# strip.net
KiCad netlist of a schematic drawn in EAGLE
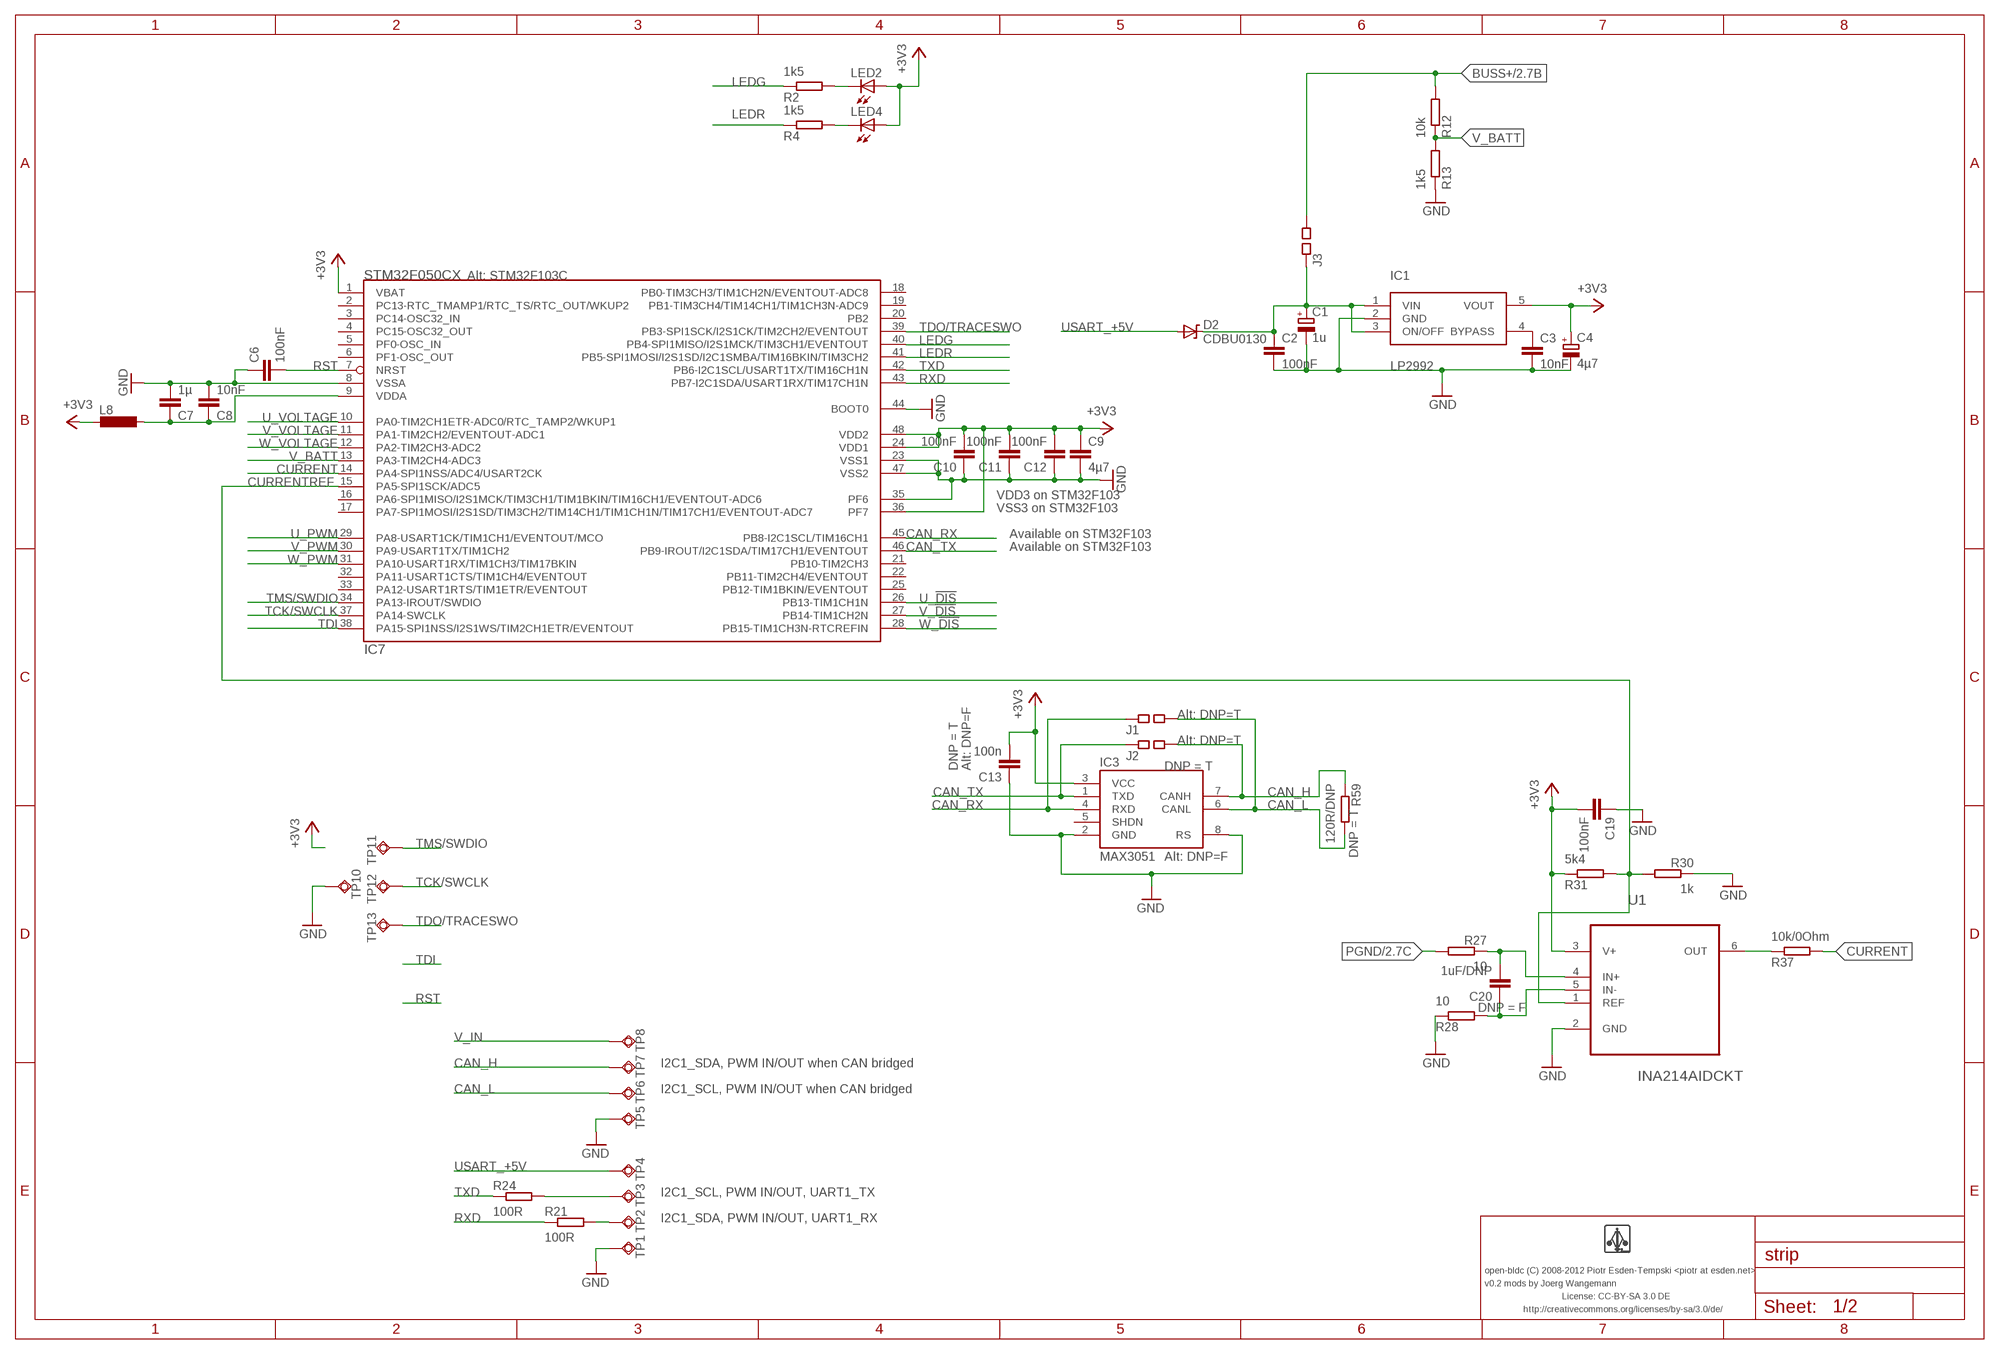
[diagram p0: schematic, sheet 1]
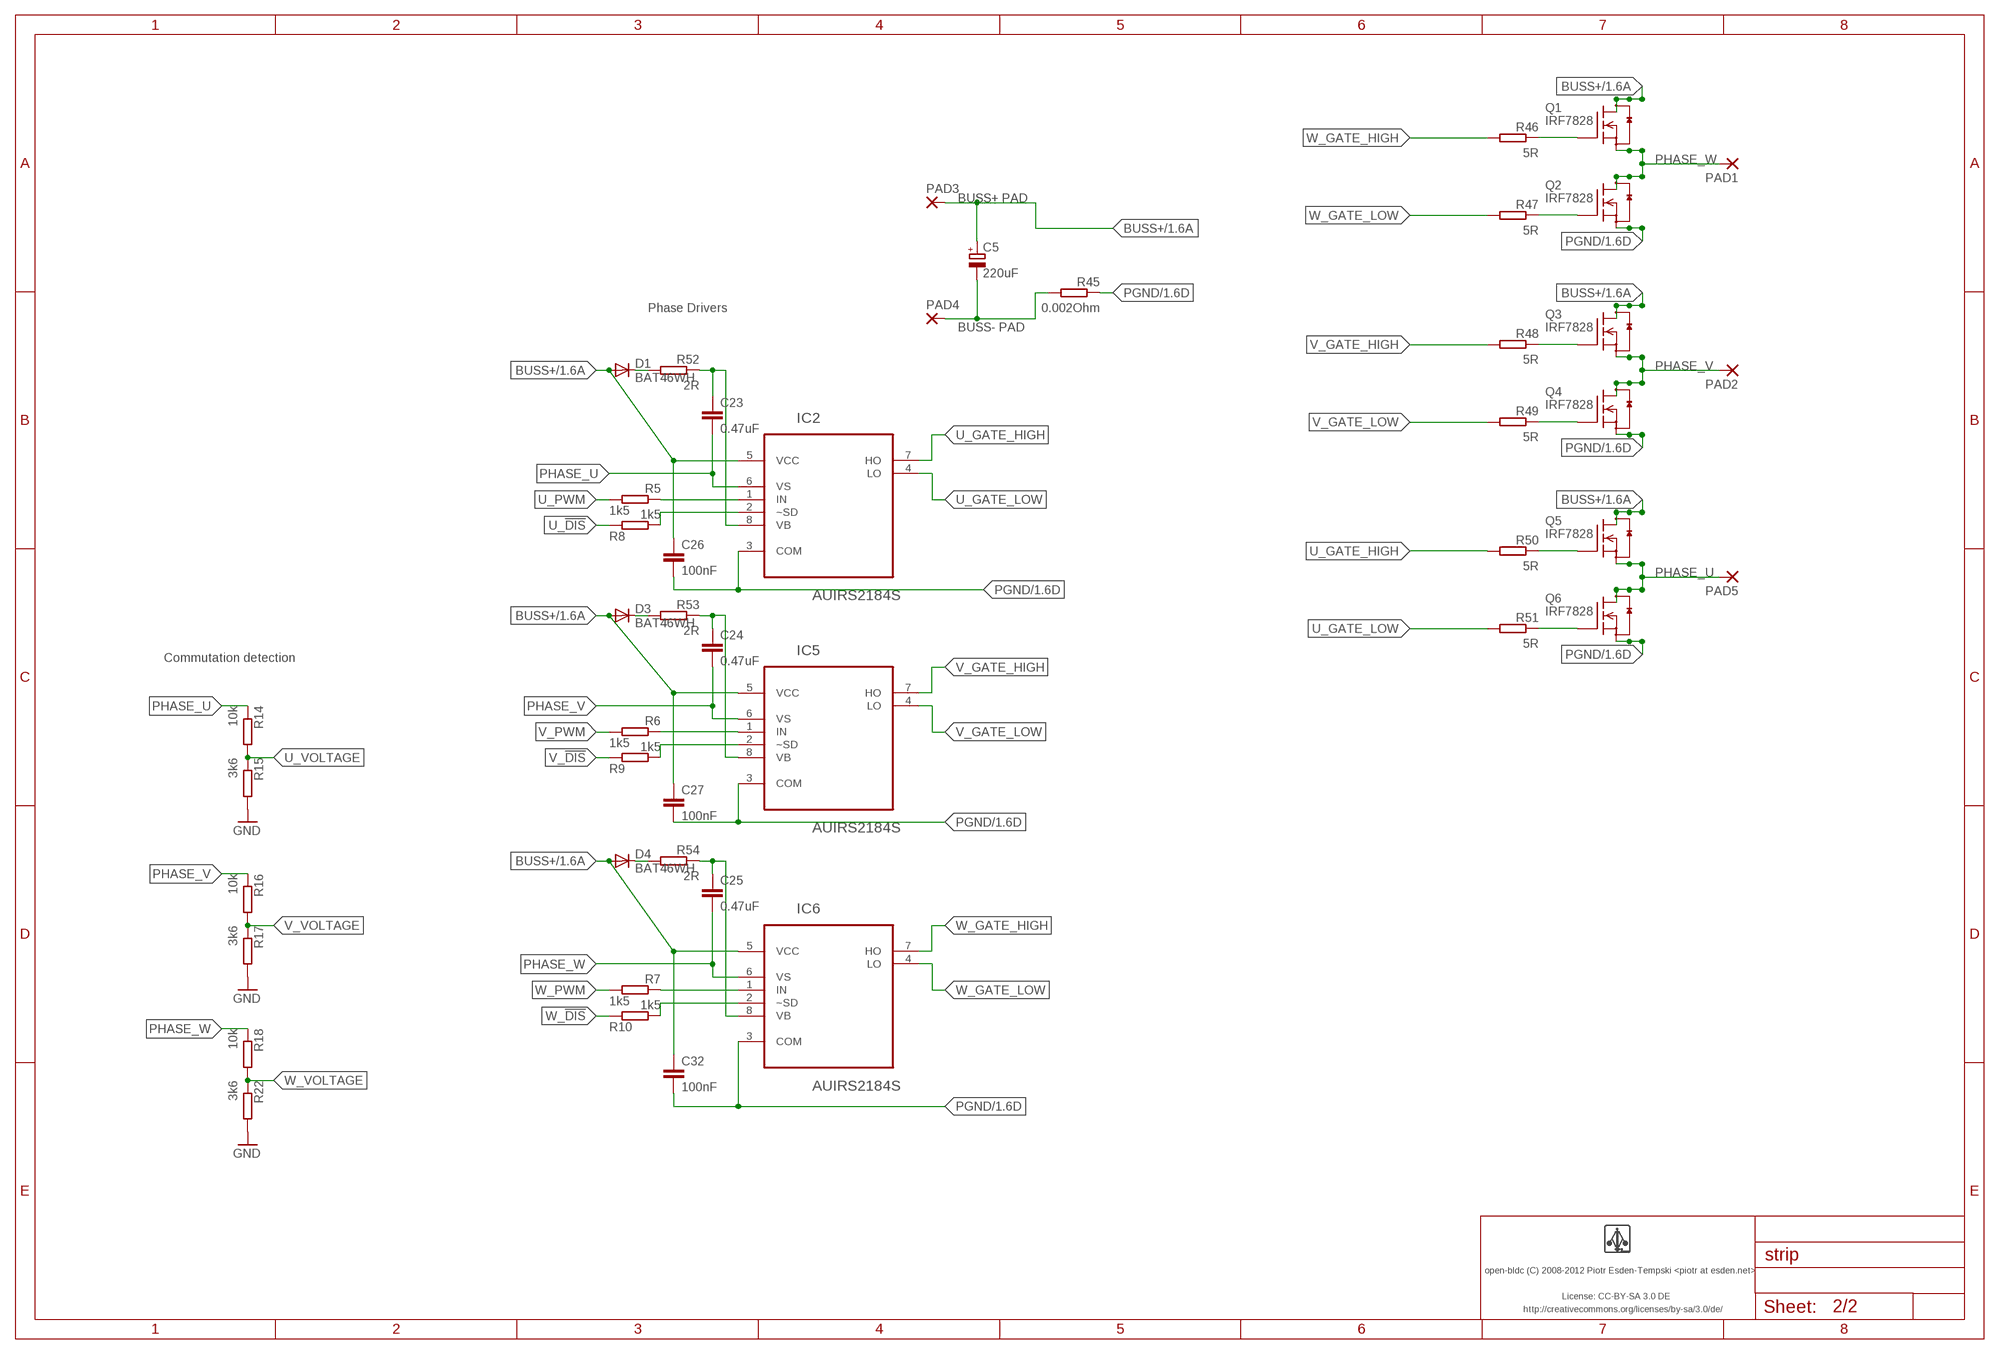
[diagram p1: schematic, sheet 2]

(export (version "E")
  (design (tool "Eeschema 10.0.6"))
  (components
    (comp (ref "C5")
      (value "220uF")
      (footprint "eagle-import:7343_D")
      (fields (field (name "PARTNO") "cap-tan-D-220u-16v"))
      (libsource (lib "eagle-import") (part "CAPACITOR-POLD"))
    )
    (comp (ref "C23")
      (value "0.47uF")
      (footprint "eagle-import:0603-CAP")
      (fields (field (name "PARTNO") "cap-tan-0603-1u"))
      (libsource (lib "eagle-import") (part "CAPACITOR-0603"))
    )
    (comp (ref "C24")
      (value "0.47uF")
      (footprint "eagle-import:0603-CAP")
      (fields (field (name "PARTNO") "cap-tan-0603-1u"))
      (libsource (lib "eagle-import") (part "CAPACITOR-0603"))
    )
    (comp (ref "C25")
      (value "0.47uF")
      (footprint "eagle-import:0603-CAP")
      (fields (field (name "PARTNO") "cap-tan-0603-1u"))
      (libsource (lib "eagle-import") (part "CAPACITOR-0603"))
    )
    (comp (ref "C26")
      (value "100nF")
      (footprint "eagle-import:0603-CAP")
      (fields (field (name "PARTNO") "cap-cer-0402-100n"))
      (libsource (lib "eagle-import") (part "CAPACITOR-0603"))
    )
    (comp (ref "C27")
      (value "100nF")
      (footprint "eagle-import:0603-CAP")
      (fields (field (name "PARTNO") "cap-cer-0402-100n"))
      (libsource (lib "eagle-import") (part "CAPACITOR-0603"))
    )
    (comp (ref "C32")
      (value "100nF")
      (footprint "eagle-import:0603-CAP")
      (fields (field (name "PARTNO") "cap-cer-0402-100n"))
      (libsource (lib "eagle-import") (part "CAPACITOR-0603"))
    )
    (comp (ref "D1")
      (value "BAT46WH")
      (footprint "eagle-import:SOD-123-DIO")
      (libsource (lib "eagle-import") (part "DIODE-SOD-123"))
    )
    (comp (ref "D3")
      (value "BAT46WH")
      (footprint "eagle-import:SOD-123-DIO")
      (libsource (lib "eagle-import") (part "DIODE-SOD-123"))
    )
    (comp (ref "D4")
      (value "BAT46WH")
      (footprint "eagle-import:SOD-123-DIO")
      (libsource (lib "eagle-import") (part "DIODE-SOD-123"))
    )
    (comp (ref "IC2")
      (value "AUIRS2184S")
      (footprint "eagle-import:SOIC127P600X175-8N")
      (fields (field (name "PARTNO") "ic-so8-mosfet-driver-buck"))
      (libsource (lib "eagle-import") (part "AUIRS2184S"))
    )
    (comp (ref "IC5")
      (value "AUIRS2184S")
      (footprint "eagle-import:SOIC127P600X175-8N")
      (fields (field (name "PARTNO") "ic-so8-mosfet-driver-buck"))
      (libsource (lib "eagle-import") (part "AUIRS2184S"))
    )
    (comp (ref "IC6")
      (value "AUIRS2184S")
      (footprint "eagle-import:SOIC127P600X175-8N")
      (fields (field (name "PARTNO") "ic-so8-mosfet-driver-buck"))
      (libsource (lib "eagle-import") (part "AUIRS2184S"))
    )
    (comp (ref "PAD1")
      (value "SMD5")
      (footprint "eagle-import:SMD2,54-5,08")
      (libsource (lib "eagle-import") (part "SMD5"))
    )
    (comp (ref "PAD2")
      (value "SMD5")
      (footprint "eagle-import:SMD2,54-5,08")
      (libsource (lib "eagle-import") (part "SMD5"))
    )
    (comp (ref "PAD3")
      (value "SMD5")
      (footprint "eagle-import:SMD2,54-5,08")
      (libsource (lib "eagle-import") (part "SMD5"))
    )
    (comp (ref "PAD4")
      (value "SMD5")
      (footprint "eagle-import:SMD2,54-5,08")
      (libsource (lib "eagle-import") (part "SMD5"))
    )
    (comp (ref "PAD5")
      (value "SMD5")
      (footprint "eagle-import:SMD2,54-5,08")
      (libsource (lib "eagle-import") (part "SMD5"))
    )
    (comp (ref "Q1")
      (value "IRF7828")
      (footprint "eagle-import:SO8")
      (fields (field (name "PARTNO") "ic-so8-mosfet-n-ch-30v-15a"))
      (libsource (lib "eagle-import") (part "IRF7828"))
    )
    (comp (ref "Q2")
      (value "IRF7828")
      (footprint "eagle-import:SO8")
      (fields (field (name "PARTNO") "ic-so8-mosfet-n-ch-30v-15a"))
      (libsource (lib "eagle-import") (part "IRF7828"))
    )
    (comp (ref "Q3")
      (value "IRF7828")
      (footprint "eagle-import:SO8")
      (fields (field (name "PARTNO") "ic-so8-mosfet-n-ch-30v-15a"))
      (libsource (lib "eagle-import") (part "IRF7828"))
    )
    (comp (ref "Q4")
      (value "IRF7828")
      (footprint "eagle-import:SO8")
      (fields (field (name "PARTNO") "ic-so8-mosfet-n-ch-30v-15a"))
      (libsource (lib "eagle-import") (part "IRF7828"))
    )
    (comp (ref "Q5")
      (value "IRF7828")
      (footprint "eagle-import:SO8")
      (fields (field (name "PARTNO") "ic-so8-mosfet-n-ch-30v-15a"))
      (libsource (lib "eagle-import") (part "IRF7828"))
    )
    (comp (ref "Q6")
      (value "IRF7828")
      (footprint "eagle-import:SO8")
      (fields (field (name "PARTNO") "ic-so8-mosfet-n-ch-30v-15a"))
      (libsource (lib "eagle-import") (part "IRF7828"))
    )
    (comp (ref "R5")
      (value "1k5")
      (footprint "eagle-import:0402-RES")
      (fields (field (name "PARTNO") "res-0402-1k5"))
      (libsource (lib "eagle-import") (part "RESISTOR-0402"))
    )
    (comp (ref "R6")
      (value "1k5")
      (footprint "eagle-import:0402-RES")
      (fields (field (name "PARTNO") "res-0402-1k5"))
      (libsource (lib "eagle-import") (part "RESISTOR-0402"))
    )
    (comp (ref "R7")
      (value "1k5")
      (footprint "eagle-import:0402-RES")
      (fields (field (name "PARTNO") "res-0402-1k5"))
      (libsource (lib "eagle-import") (part "RESISTOR-0402"))
    )
    (comp (ref "R8")
      (value "1k5")
      (footprint "eagle-import:0402-RES")
      (fields (field (name "PARTNO") "res-0402-1k5"))
      (libsource (lib "eagle-import") (part "RESISTOR-0402"))
    )
    (comp (ref "R9")
      (value "1k5")
      (footprint "eagle-import:0402-RES")
      (fields (field (name "PARTNO") "res-0402-1k5"))
      (libsource (lib "eagle-import") (part "RESISTOR-0402"))
    )
    (comp (ref "R10")
      (value "1k5")
      (footprint "eagle-import:0402-RES")
      (fields (field (name "PARTNO") "res-0402-1k5"))
      (libsource (lib "eagle-import") (part "RESISTOR-0402"))
    )
    (comp (ref "R14")
      (value "10k")
      (footprint "eagle-import:0402-RES")
      (fields (field (name "PARTNO") "res-0402-10k"))
      (libsource (lib "eagle-import") (part "RESISTOR-0402"))
    )
    (comp (ref "R15")
      (value "3k6")
      (footprint "eagle-import:0402-RES")
      (libsource (lib "eagle-import") (part "RESISTOR-0402"))
    )
    (comp (ref "R16")
      (value "10k")
      (footprint "eagle-import:0402-RES")
      (fields (field (name "PARTNO") "res-0402-10k"))
      (libsource (lib "eagle-import") (part "RESISTOR-0402"))
    )
    (comp (ref "R17")
      (value "3k6")
      (footprint "eagle-import:0402-RES")
      (libsource (lib "eagle-import") (part "RESISTOR-0402"))
    )
    (comp (ref "R18")
      (value "10k")
      (footprint "eagle-import:0402-RES")
      (fields (field (name "PARTNO") "res-0402-10k"))
      (libsource (lib "eagle-import") (part "RESISTOR-0402"))
    )
    (comp (ref "R22")
      (value "3k6")
      (footprint "eagle-import:0402-RES")
      (libsource (lib "eagle-import") (part "RESISTOR-0402"))
    )
    (comp (ref "R45")
      (value "0.002Ohm")
      (footprint "eagle-import:1206-RES")
      (fields (field (name "PARTNO") "res-1206-0005"))
      (libsource (lib "eagle-import") (part "RESISTOR-1206"))
    )
    (comp (ref "R46")
      (value "5R")
      (footprint "eagle-import:0603-RES")
      (fields (field (name "PARTNO") "res-0402-10"))
      (libsource (lib "eagle-import") (part "RESISTOR-0603"))
    )
    (comp (ref "R47")
      (value "5R")
      (footprint "eagle-import:0603-RES")
      (fields (field (name "PARTNO") "res-0402-10"))
      (libsource (lib "eagle-import") (part "RESISTOR-0603"))
    )
    (comp (ref "R48")
      (value "5R")
      (footprint "eagle-import:0603-RES")
      (fields (field (name "PARTNO") "res-0402-10"))
      (libsource (lib "eagle-import") (part "RESISTOR-0603"))
    )
    (comp (ref "R49")
      (value "5R")
      (footprint "eagle-import:0603-RES")
      (fields (field (name "PARTNO") "res-0402-10"))
      (libsource (lib "eagle-import") (part "RESISTOR-0603"))
    )
    (comp (ref "R50")
      (value "5R")
      (footprint "eagle-import:0603-RES")
      (fields (field (name "PARTNO") "res-0402-10"))
      (libsource (lib "eagle-import") (part "RESISTOR-0603"))
    )
    (comp (ref "R51")
      (value "5R")
      (footprint "eagle-import:0603-RES")
      (fields (field (name "PARTNO") "res-0402-10"))
      (libsource (lib "eagle-import") (part "RESISTOR-0603"))
    )
    (comp (ref "R52")
      (value "2R")
      (footprint "eagle-import:0402-RES")
      (fields (field (name "PARTNO") "res-0402-10"))
      (libsource (lib "eagle-import") (part "RESISTOR-0402"))
    )
    (comp (ref "R53")
      (value "2R")
      (footprint "eagle-import:0402-RES")
      (fields (field (name "PARTNO") "res-0402-10"))
      (libsource (lib "eagle-import") (part "RESISTOR-0402"))
    )
    (comp (ref "R54")
      (value "2R")
      (footprint "eagle-import:0402-RES")
      (fields (field (name "PARTNO") "res-0402-10"))
      (libsource (lib "eagle-import") (part "RESISTOR-0402"))
    )
    (comp (ref "U$2")
      (value "LOGO")
      (footprint "eagle-import:LOGO_SILK_SMALL")
      (libsource (lib "eagle-import") (part "LOGO-SILK-SMALL"))
    )
    (comp (ref "C1")
      (value "1u")
      (footprint "eagle-import:0805-POL-CAP")
      (fields (field (name "PARTNO") "cap-cer-0805-1u-35v"))
      (libsource (lib "eagle-import") (part "CAPACITOR-POL-0805"))
    )
    (comp (ref "C2")
      (value "100nF")
      (footprint "eagle-import:0402-CAP")
      (fields (field (name "PARTNO") "cap-cer-0402-100n"))
      (libsource (lib "eagle-import") (part "CAPACITOR-0402"))
    )
    (comp (ref "C3")
      (value "10nF")
      (footprint "eagle-import:0402-CAP")
      (fields (field (name "PARTNO") "cap-cer-0402-10n"))
      (libsource (lib "eagle-import") (part "CAPACITOR-0402"))
    )
    (comp (ref "C4")
      (value "4µ7")
      (footprint "eagle-import:0805-POL-CAP")
      (fields (field (name "PARTNO") "cap-cer-0805-4u7-16v"))
      (libsource (lib "eagle-import") (part "CAPACITOR-POL-0805"))
    )
    (comp (ref "C6")
      (value "100nF")
      (footprint "eagle-import:0402-CAP")
      (fields (field (name "PARTNO") "cap-cer-0402-100n"))
      (libsource (lib "eagle-import") (part "CAPACITOR-0402"))
    )
    (comp (ref "C7")
      (value "1µ")
      (footprint "eagle-import:0402-CAP")
      (fields (field (name "PARTNO") "cap-cer-0402-1u"))
      (libsource (lib "eagle-import") (part "CAPACITOR-0402"))
    )
    (comp (ref "C8")
      (value "10nF")
      (footprint "eagle-import:0402-CAP")
      (fields (field (name "PARTNO") "cap-cer-0402-10n"))
      (libsource (lib "eagle-import") (part "CAPACITOR-0402"))
    )
    (comp (ref "C9")
      (value "4µ7")
      (footprint "eagle-import:0805-CAP")
      (fields (field (name "PARTNO") "cap-cer-0805-4u7"))
      (libsource (lib "eagle-import") (part "CAPACITOR-0805"))
    )
    (comp (ref "C10")
      (value "100nF")
      (footprint "eagle-import:0402-CAP")
      (fields (field (name "PARTNO") "cap-cer-0402-100n"))
      (libsource (lib "eagle-import") (part "CAPACITOR-0402"))
    )
    (comp (ref "C11")
      (value "100nF")
      (footprint "eagle-import:0402-CAP")
      (fields (field (name "PARTNO") "cap-cer-0402-100n"))
      (libsource (lib "eagle-import") (part "CAPACITOR-0402"))
    )
    (comp (ref "C12")
      (value "100nF")
      (footprint "eagle-import:0402-CAP")
      (fields (field (name "PARTNO") "cap-cer-0402-100n"))
      (libsource (lib "eagle-import") (part "CAPACITOR-0402"))
    )
    (comp (ref "C13")
      (value "100n")
      (footprint "eagle-import:0402-CAP")
      (fields (field (name "DNP") "T") (field (name "PARTNO") "cap-cer-0402-100n"))
      (libsource (lib "eagle-import") (part "CAPACITOR-0402"))
    )
    (comp (ref "C19")
      (value "100nF")
      (footprint "eagle-import:0402-CAP")
      (fields (field (name "PARTNO") "cap-cer-0402-100n"))
      (libsource (lib "eagle-import") (part "CAPACITOR-0402"))
    )
    (comp (ref "C20")
      (value "1uF/DNP")
      (footprint "eagle-import:0603-CAP")
      (fields (field (name "DNP") "F") (field (name "PARTNO") "cap-cer-0402-100n"))
      (libsource (lib "eagle-import") (part "CAPACITOR-0603"))
    )
    (comp (ref "D2")
      (value "CDBU0130")
      (footprint "eagle-import:0603-DIO")
      (fields (field (name "PARTNO") "diode-0603"))
      (libsource (lib "eagle-import") (part "DIODE-ZENER-0603"))
    )
    (comp (ref "IC1")
      (value "LP2992")
      (footprint "eagle-import:SOT23-5")
      (fields (field (name "PARTNO") "vreg-sot-23-5-3v3"))
      (libsource (lib "eagle-import") (part "LP2992"))
    )
    (comp (ref "IC3")
      (value "MAX3051")
      (footprint "eagle-import:SO8")
      (fields (field (name "DNP") "T"))
      (libsource (lib "eagle-import") (part "MAX3051"))
    )
    (comp (ref "IC7")
      (value "STM32F050CX")
      (footprint "eagle-import:LQFP48")
      (fields (field (name "PARTNO") "mcu-tqfp-32-stm32f05"))
      (libsource (lib "eagle-import") (part "STM32F050CX"))
    )
    (comp (ref "J1")
      (value "SQ_JMP-0402")
      (footprint "eagle-import:0402-SQJMP")
      (fields (field (name "PARTNO") "res-0402-0"))
      (libsource (lib "eagle-import") (part "SQ_JMP-0402"))
    )
    (comp (ref "J2")
      (value "SQ_JMP-0402")
      (footprint "eagle-import:0402-SQJMP")
      (fields (field (name "PARTNO") "res-0402-0"))
      (libsource (lib "eagle-import") (part "SQ_JMP-0402"))
    )
    (comp (ref "J3")
      (value "SQ_JMP-0402")
      (footprint "eagle-import:0402-SQJMP")
      (fields (field (name "PARTNO") "res-0402-0"))
      (libsource (lib "eagle-import") (part "SQ_JMP-0402"))
    )
    (comp (ref "L8")
      (value "INDUCTOR-0603")
      (footprint "eagle-import:0603-IND")
      (fields (field (name "PARTNO") "ferrite-0603-600ohm"))
      (libsource (lib "eagle-import") (part "INDUCTOR-0603"))
    )
    (comp (ref "LED2")
      (value "GREEN")
      (footprint "eagle-import:0402-LED")
      (fields (field (name "PARTNO") "led-0402-green"))
      (libsource (lib "eagle-import") (part "LED-0402"))
    )
    (comp (ref "LED4")
      (value "RED")
      (footprint "eagle-import:0402-LED")
      (fields (field (name "PARTNO") "led-0402-green"))
      (libsource (lib "eagle-import") (part "LED-0402"))
    )
    (comp (ref "R2")
      (value "1k5")
      (footprint "eagle-import:0402-RES")
      (fields (field (name "PARTNO") "res-0402-1k5"))
      (libsource (lib "eagle-import") (part "RESISTOR-0402"))
    )
    (comp (ref "R4")
      (value "1k5")
      (footprint "eagle-import:0402-RES")
      (fields (field (name "PARTNO") "res-0402-1k5"))
      (libsource (lib "eagle-import") (part "RESISTOR-0402"))
    )
    (comp (ref "R12")
      (value "10k")
      (footprint "eagle-import:0402-RES")
      (fields (field (name "PARTNO") "res-0402-10k"))
      (libsource (lib "eagle-import") (part "RESISTOR-0402"))
    )
    (comp (ref "R13")
      (value "1k5")
      (footprint "eagle-import:0402-RES")
      (fields (field (name "PARTNO") "res-0402-1k5"))
      (libsource (lib "eagle-import") (part "RESISTOR-0402"))
    )
    (comp (ref "R21")
      (value "100R")
      (footprint "eagle-import:0402-RES")
      (fields (field (name "PARTNO") "res-0402-100"))
      (libsource (lib "eagle-import") (part "RESISTOR-0402"))
    )
    (comp (ref "R24")
      (value "100R")
      (footprint "eagle-import:0402-RES")
      (fields (field (name "PARTNO") "res-0402-100"))
      (libsource (lib "eagle-import") (part "RESISTOR-0402"))
    )
    (comp (ref "R27")
      (value "10")
      (footprint "eagle-import:0402-RES")
      (fields (field (name "PARTNO") "res-0402-665"))
      (libsource (lib "eagle-import") (part "RESISTOR-0402"))
    )
    (comp (ref "R28")
      (value "10")
      (footprint "eagle-import:0402-RES")
      (fields (field (name "PARTNO") "res-0402-560"))
      (libsource (lib "eagle-import") (part "RESISTOR-0402"))
    )
    (comp (ref "R30")
      (value "1k")
      (footprint "eagle-import:0402-RES")
      (fields (field (name "PARTNO") "res-0402-1k"))
      (libsource (lib "eagle-import") (part "RESISTOR-0402"))
    )
    (comp (ref "R31")
      (value "5k4")
      (footprint "eagle-import:0402-RES")
      (fields (field (name "PARTNO") "res-0402-5k36"))
      (libsource (lib "eagle-import") (part "RESISTOR-0402"))
    )
    (comp (ref "R37")
      (value "10k/0Ohm")
      (footprint "eagle-import:0402-RES")
      (fields (field (name "PARTNO") "res-0402-0"))
      (libsource (lib "eagle-import") (part "RESISTOR-0402"))
    )
    (comp (ref "R59")
      (value "120R/DNP")
      (footprint "eagle-import:0402-RES")
      (fields (field (name "DNP") "T") (field (name "PARTNO") "res-0402-60.4"))
      (libsource (lib "eagle-import") (part "RESISTOR-0402"))
    )
    (comp (ref "TP1")
      (value "TPSQTP20SQ")
      (footprint "eagle-import:TP20SQ")
      (libsource (lib "eagle-import") (part "TPSQTP20SQ"))
    )
    (comp (ref "TP2")
      (value "TPSQTP20SQ")
      (footprint "eagle-import:TP20SQ")
      (libsource (lib "eagle-import") (part "TPSQTP20SQ"))
    )
    (comp (ref "TP3")
      (value "TPSQTP20SQ")
      (footprint "eagle-import:TP20SQ")
      (libsource (lib "eagle-import") (part "TPSQTP20SQ"))
    )
    (comp (ref "TP4")
      (value "TPSQTP20SQ")
      (footprint "eagle-import:TP20SQ")
      (libsource (lib "eagle-import") (part "TPSQTP20SQ"))
    )
    (comp (ref "TP5")
      (value "TPSQTP20SQ")
      (footprint "eagle-import:TP20SQ")
      (libsource (lib "eagle-import") (part "TPSQTP20SQ"))
    )
    (comp (ref "TP6")
      (value "TPSQTP20SQ")
      (footprint "eagle-import:TP20SQ")
      (libsource (lib "eagle-import") (part "TPSQTP20SQ"))
    )
    (comp (ref "TP7")
      (value "TPSQTP20SQ")
      (footprint "eagle-import:TP20SQ")
      (libsource (lib "eagle-import") (part "TPSQTP20SQ"))
    )
    (comp (ref "TP8")
      (value "TPSQTP20SQ")
      (footprint "eagle-import:TP20SQ")
      (libsource (lib "eagle-import") (part "TPSQTP20SQ"))
    )
    (comp (ref "TP10")
      (value "TPSQTP11SQ")
      (footprint "eagle-import:TP11SQ")
      (libsource (lib "eagle-import") (part "TPSQTP11SQ"))
    )
    (comp (ref "TP11")
      (value "TPSQTP11SQ")
      (footprint "eagle-import:TP11SQ")
      (libsource (lib "eagle-import") (part "TPSQTP11SQ"))
    )
    (comp (ref "TP12")
      (value "TPSQTP11SQ")
      (footprint "eagle-import:TP11SQ")
      (libsource (lib "eagle-import") (part "TPSQTP11SQ"))
    )
    (comp (ref "TP13")
      (value "TPSQTP11SQ")
      (footprint "eagle-import:TP11SQ")
      (libsource (lib "eagle-import") (part "TPSQTP11SQ"))
    )
    (comp (ref "U$1")
      (value "LOGO")
      (footprint "eagle-import:LOGO_SILK_SMALL")
      (libsource (lib "eagle-import") (part "LOGO-SILK-SMALL"))
    )
    (comp (ref "U1")
      (value "INA214AIDCKT")
      (footprint "eagle-import:SOT65P210X110-6N")
      (libsource (lib "eagle-import") (part "INA214AIDCKT"))
    )
  )
  (nets
    (net (code "1") (name "+3V3") (class "Default")
      (node (ref "C10") (pin "P$2") (pinfunction "2_P$2") (pintype "passive"))
      (node (ref "C11") (pin "P$2") (pinfunction "2_P$2") (pintype "passive"))
      (node (ref "C12") (pin "P$2") (pinfunction "2_P$2") (pintype "passive"))
      (node (ref "C13") (pin "P$2") (pinfunction "2_P$2") (pintype "passive"))
      (node (ref "C19") (pin "P$2") (pinfunction "2_P$2") (pintype "passive"))
      (node (ref "C4") (pin "+") (pinfunction "+_+") (pintype "passive"))
      (node (ref "C9") (pin "P$1") (pinfunction "1_P$1") (pintype "passive"))
      (node (ref "IC1") (pin "5") (pinfunction "VOUT_5") (pintype "bidirectional"))
      (node (ref "IC3") (pin "3") (pinfunction "VCC_3") (pintype "bidirectional"))
      (node (ref "IC7") (pin "1") (pinfunction "VBAT_1") (pintype "power_in"))
      (node (ref "IC7") (pin "24") (pinfunction "VDD1_24") (pintype "power_in"))
      (node (ref "IC7") (pin "36") (pinfunction "PF7_36") (pintype "power_in"))
      (node (ref "IC7") (pin "48") (pinfunction "VDD2_48") (pintype "power_in"))
      (node (ref "L8") (pin "P$2") (pinfunction "2_P$2") (pintype "passive"))
      (node (ref "LED2") (pin "A") (pinfunction "A_A") (pintype "passive"))
      (node (ref "LED4") (pin "A") (pinfunction "A_A") (pintype "passive"))
      (node (ref "R31") (pin "P$1") (pinfunction "1_P$1") (pintype "passive"))
      (node (ref "U1") (pin "3") (pinfunction "V+_3") (pintype "power_in"))
    )
    (net (code "2") (name "BUSS+") (class "Default")
      (node (ref "C26") (pin "P$1") (pinfunction "1_P$1") (pintype "passive"))
      (node (ref "C27") (pin "P$1") (pinfunction "1_P$1") (pintype "passive"))
      (node (ref "C32") (pin "P$1") (pinfunction "1_P$1") (pintype "passive"))
      (node (ref "C5") (pin "+") (pinfunction "+_+") (pintype "passive"))
      (node (ref "D1") (pin "A") (pinfunction "A_A") (pintype "passive"))
      (node (ref "D3") (pin "A") (pinfunction "A_A") (pintype "passive"))
      (node (ref "D4") (pin "A") (pinfunction "A_A") (pintype "passive"))
      (node (ref "IC2") (pin "5") (pinfunction "VCC_5") (pintype "power_in"))
      (node (ref "IC5") (pin "5") (pinfunction "VCC_5") (pintype "power_in"))
      (node (ref "IC6") (pin "5") (pinfunction "VCC_5") (pintype "power_in"))
      (node (ref "J3") (pin "P$2") (pinfunction "2_P$2") (pintype "passive"))
      (node (ref "PAD3") (pin "1") (pinfunction "P_1") (pintype "passive"))
      (node (ref "Q1") (pin "5") (pinfunction "D1_5") (pintype "passive"))
      (node (ref "Q1") (pin "6") (pinfunction "D2_6") (pintype "passive"))
      (node (ref "Q1") (pin "7") (pinfunction "D3_7") (pintype "passive"))
      (node (ref "Q1") (pin "8") (pinfunction "D4_8") (pintype "passive"))
      (node (ref "Q3") (pin "5") (pinfunction "D1_5") (pintype "passive"))
      (node (ref "Q3") (pin "6") (pinfunction "D2_6") (pintype "passive"))
      (node (ref "Q3") (pin "7") (pinfunction "D3_7") (pintype "passive"))
      (node (ref "Q3") (pin "8") (pinfunction "D4_8") (pintype "passive"))
      (node (ref "Q5") (pin "5") (pinfunction "D1_5") (pintype "passive"))
      (node (ref "Q5") (pin "6") (pinfunction "D2_6") (pintype "passive"))
      (node (ref "Q5") (pin "7") (pinfunction "D3_7") (pintype "passive"))
      (node (ref "Q5") (pin "8") (pinfunction "D4_8") (pintype "passive"))
      (node (ref "R12") (pin "P$2") (pinfunction "2_P$2") (pintype "passive"))
    )
    (net (code "3") (name "CAN_H") (class "Default")
      (node (ref "IC3") (pin "7") (pinfunction "CANH_7") (pintype "bidirectional"))
      (node (ref "J2") (pin "P$2") (pinfunction "2_P$2") (pintype "passive"))
      (node (ref "R59") (pin "P$1") (pinfunction "1_P$1") (pintype "passive"))
      (node (ref "TP7") (pin "TP") (pinfunction "TP_TP") (pintype "input"))
    )
    (net (code "4") (name "CAN_L") (class "Default")
      (node (ref "IC3") (pin "6") (pinfunction "CANL_6") (pintype "bidirectional"))
      (node (ref "J1") (pin "P$2") (pinfunction "2_P$2") (pintype "passive"))
      (node (ref "R59") (pin "P$2") (pinfunction "2_P$2") (pintype "passive"))
      (node (ref "TP6") (pin "TP") (pinfunction "TP_TP") (pintype "input"))
    )
    (net (code "5") (name "CAN_RX") (class "Default")
      (node (ref "IC3") (pin "4") (pinfunction "RXD_4") (pintype "bidirectional"))
      (node (ref "IC7") (pin "45") (pinfunction "PB8-I2C1SCL/TIM16CH1_45") (pintype "bidirectional"))
      (node (ref "J1") (pin "P$1") (pinfunction "1_P$1") (pintype "passive"))
    )
    (net (code "6") (name "CAN_TX") (class "Default")
      (node (ref "IC3") (pin "1") (pinfunction "TXD_1") (pintype "bidirectional"))
      (node (ref "IC7") (pin "46") (pinfunction "PB9-IROUT/I2C1SDA/TIM17CH1/EVENTOUT_46") (pintype "bidirectional"))
      (node (ref "J2") (pin "P$1") (pinfunction "1_P$1") (pintype "passive"))
    )
    (net (code "7") (name "CURRENT") (class "Default")
      (node (ref "IC7") (pin "14") (pinfunction "PA4-SPI1NSS/ADC4/USART2CK_14") (pintype "bidirectional"))
      (node (ref "R37") (pin "P$2") (pinfunction "2_P$2") (pintype "passive"))
    )
    (net (code "8") (name "CURRENTREF") (class "Default")
      (node (ref "IC7") (pin "15") (pinfunction "PA5-SPI1SCK/ADC5_15") (pintype "bidirectional"))
      (node (ref "R30") (pin "P$2") (pinfunction "2_P$2") (pintype "passive"))
      (node (ref "R31") (pin "P$2") (pinfunction "2_P$2") (pintype "passive"))
      (node (ref "U1") (pin "1") (pinfunction "REF_1") (pintype "input"))
    )
    (net (code "9") (name "GND") (class "Default")
      (node (ref "C1") (pin "-") (pinfunction "-_-") (pintype "passive"))
      (node (ref "C10") (pin "P$1") (pinfunction "1_P$1") (pintype "passive"))
      (node (ref "C11") (pin "P$1") (pinfunction "1_P$1") (pintype "passive"))
      (node (ref "C12") (pin "P$1") (pinfunction "1_P$1") (pintype "passive"))
      (node (ref "C13") (pin "P$1") (pinfunction "1_P$1") (pintype "passive"))
      (node (ref "C19") (pin "P$1") (pinfunction "1_P$1") (pintype "passive"))
      (node (ref "C2") (pin "P$2") (pinfunction "2_P$2") (pintype "passive"))
      (node (ref "C3") (pin "P$2") (pinfunction "2_P$2") (pintype "passive"))
      (node (ref "C4") (pin "-") (pinfunction "-_-") (pintype "passive"))
      (node (ref "C5") (pin "-") (pinfunction "-_-") (pintype "passive"))
      (node (ref "C6") (pin "P$1") (pinfunction "1_P$1") (pintype "passive"))
      (node (ref "C7") (pin "P$2") (pinfunction "2_P$2") (pintype "passive"))
      (node (ref "C8") (pin "P$2") (pinfunction "2_P$2") (pintype "passive"))
      (node (ref "C9") (pin "P$2") (pinfunction "2_P$2") (pintype "passive"))
      (node (ref "IC1") (pin "2") (pinfunction "GND_2") (pintype "bidirectional"))
      (node (ref "IC3") (pin "2") (pinfunction "GND_2") (pintype "bidirectional"))
      (node (ref "IC3") (pin "8") (pinfunction "RS_8") (pintype "bidirectional"))
      (node (ref "IC7") (pin "23") (pinfunction "VSS1_23") (pintype "power_in"))
      (node (ref "IC7") (pin "35") (pinfunction "PF6_35") (pintype "power_in"))
      (node (ref "IC7") (pin "44") (pinfunction "BOOT0_44") (pintype "input"))
      (node (ref "IC7") (pin "47") (pinfunction "VSS2_47") (pintype "power_in"))
      (node (ref "IC7") (pin "8") (pinfunction "VSSA_8") (pintype "power_in"))
      (node (ref "PAD4") (pin "1") (pinfunction "P_1") (pintype "passive"))
      (node (ref "R13") (pin "P$1") (pinfunction "1_P$1") (pintype "passive"))
      (node (ref "R15") (pin "P$2") (pinfunction "2_P$2") (pintype "passive"))
      (node (ref "R17") (pin "P$2") (pinfunction "2_P$2") (pintype "passive"))
      (node (ref "R22") (pin "P$2") (pinfunction "2_P$2") (pintype "passive"))
      (node (ref "R28") (pin "P$1") (pinfunction "1_P$1") (pintype "passive"))
      (node (ref "R30") (pin "P$1") (pinfunction "1_P$1") (pintype "passive"))
      (node (ref "R45") (pin "P$2") (pinfunction "2_P$2") (pintype "passive"))
      (node (ref "TP1") (pin "TP") (pinfunction "TP_TP") (pintype "input"))
      (node (ref "TP10") (pin "TP") (pinfunction "TP_TP") (pintype "input"))
      (node (ref "TP5") (pin "TP") (pinfunction "TP_TP") (pintype "input"))
      (node (ref "U1") (pin "2") (pinfunction "GND_2") (pintype "passive"))
    )
    (net (code "10") (name "LEDG") (class "Default")
      (node (ref "IC7") (pin "40") (pinfunction "PB4-SPI1MISO/I2S1MCK/TIM3CH1/EVENTOUT_40") (pintype "bidirectional"))
      (node (ref "R2") (pin "P$1") (pinfunction "1_P$1") (pintype "passive"))
    )
    (net (code "11") (name "LEDR") (class "Default")
      (node (ref "IC7") (pin "41") (pinfunction "PB5-SPI1MOSI/I2S1SD/I2C1SMBA/TIM16BKIN/TIM3CH2_41") (pintype "bidirectional"))
      (node (ref "R4") (pin "P$1") (pinfunction "1_P$1") (pintype "passive"))
    )
    (net (code "12") (name "Net-(C3-1)") (class "Default")
      (node (ref "C3") (pin "P$1") (pinfunction "1_P$1") (pintype "passive"))
      (node (ref "IC1") (pin "4") (pinfunction "BYPASS_4") (pintype "bidirectional"))
    )
    (net (code "13") (name "Net-(C7-1)") (class "Default")
      (node (ref "C7") (pin "P$1") (pinfunction "1_P$1") (pintype "passive"))
      (node (ref "C8") (pin "P$1") (pinfunction "1_P$1") (pintype "passive"))
      (node (ref "IC7") (pin "9") (pinfunction "VDDA_9") (pintype "power_in"))
      (node (ref "L8") (pin "P$1") (pinfunction "1_P$1") (pintype "passive"))
    )
    (net (code "14") (name "Net-(C20-1)") (class "Default")
      (node (ref "C20") (pin "P$1") (pinfunction "1_P$1") (pintype "passive"))
      (node (ref "R28") (pin "P$2") (pinfunction "2_P$2") (pintype "passive"))
      (node (ref "U1") (pin "5") (pinfunction "IN-_5") (pintype "input"))
    )
    (net (code "15") (name "Net-(C20-2)") (class "Default")
      (node (ref "C20") (pin "P$2") (pinfunction "2_P$2") (pintype "passive"))
      (node (ref "R27") (pin "P$1") (pinfunction "1_P$1") (pintype "passive"))
      (node (ref "U1") (pin "4") (pinfunction "IN+_4") (pintype "input"))
    )
    (net (code "16") (name "Net-(C23-1)") (class "Default")
      (node (ref "C23") (pin "P$1") (pinfunction "1_P$1") (pintype "passive"))
      (node (ref "IC2") (pin "8") (pinfunction "VB_8") (pintype "input"))
      (node (ref "R52") (pin "P$1") (pinfunction "1_P$1") (pintype "passive"))
    )
    (net (code "17") (name "Net-(C24-1)") (class "Default")
      (node (ref "C24") (pin "P$1") (pinfunction "1_P$1") (pintype "passive"))
      (node (ref "IC5") (pin "8") (pinfunction "VB_8") (pintype "input"))
      (node (ref "R53") (pin "P$1") (pinfunction "1_P$1") (pintype "passive"))
    )
    (net (code "18") (name "Net-(C25-1)") (class "Default")
      (node (ref "C25") (pin "P$1") (pinfunction "1_P$1") (pintype "passive"))
      (node (ref "IC6") (pin "8") (pinfunction "VB_8") (pintype "input"))
      (node (ref "R54") (pin "P$1") (pinfunction "1_P$1") (pintype "passive"))
    )
    (net (code "19") (name "Net-(IC2-IN)") (class "Default")
      (node (ref "IC2") (pin "1") (pinfunction "IN_1") (pintype "input"))
      (node (ref "R5") (pin "P$1") (pinfunction "1_P$1") (pintype "passive"))
    )
    (net (code "20") (name "Net-(IC2-~{SD})") (class "Default")
      (node (ref "IC2") (pin "2") (pinfunction "~{SD}_2") (pintype "input"))
      (node (ref "R8") (pin "P$2") (pinfunction "2_P$2") (pintype "passive"))
    )
    (net (code "21") (name "Net-(IC5-IN)") (class "Default")
      (node (ref "IC5") (pin "1") (pinfunction "IN_1") (pintype "input"))
      (node (ref "R6") (pin "P$1") (pinfunction "1_P$1") (pintype "passive"))
    )
    (net (code "22") (name "Net-(IC5-~{SD})") (class "Default")
      (node (ref "IC5") (pin "2") (pinfunction "~{SD}_2") (pintype "input"))
      (node (ref "R9") (pin "P$2") (pinfunction "2_P$2") (pintype "passive"))
    )
    (net (code "23") (name "Net-(IC6-IN)") (class "Default")
      (node (ref "IC6") (pin "1") (pinfunction "IN_1") (pintype "input"))
      (node (ref "R7") (pin "P$1") (pinfunction "1_P$1") (pintype "passive"))
    )
    (net (code "24") (name "Net-(IC6-~{SD})") (class "Default")
      (node (ref "IC6") (pin "2") (pinfunction "~{SD}_2") (pintype "input"))
      (node (ref "R10") (pin "P$2") (pinfunction "2_P$2") (pintype "passive"))
    )
    (net (code "25") (name "Net-(Q1-G)") (class "Default")
      (node (ref "Q1") (pin "4") (pinfunction "G_4") (pintype "passive"))
      (node (ref "R46") (pin "P$1") (pinfunction "1_P$1") (pintype "passive"))
    )
    (net (code "26") (name "Net-(Q2-G)") (class "Default")
      (node (ref "Q2") (pin "4") (pinfunction "G_4") (pintype "passive"))
      (node (ref "R47") (pin "P$1") (pinfunction "1_P$1") (pintype "passive"))
    )
    (net (code "27") (name "Net-(Q3-G)") (class "Default")
      (node (ref "Q3") (pin "4") (pinfunction "G_4") (pintype "passive"))
      (node (ref "R48") (pin "P$1") (pinfunction "1_P$1") (pintype "passive"))
    )
    (net (code "28") (name "Net-(Q4-G)") (class "Default")
      (node (ref "Q4") (pin "4") (pinfunction "G_4") (pintype "passive"))
      (node (ref "R49") (pin "P$1") (pinfunction "1_P$1") (pintype "passive"))
    )
    (net (code "29") (name "Net-(Q5-G)") (class "Default")
      (node (ref "Q5") (pin "4") (pinfunction "G_4") (pintype "passive"))
      (node (ref "R50") (pin "P$1") (pinfunction "1_P$1") (pintype "passive"))
    )
    (net (code "30") (name "Net-(Q6-G)") (class "Default")
      (node (ref "Q6") (pin "4") (pinfunction "G_4") (pintype "passive"))
      (node (ref "R51") (pin "P$1") (pinfunction "1_P$1") (pintype "passive"))
    )
    (net (code "31") (name "Net-(R2-2)") (class "Default")
      (node (ref "LED2") (pin "C") (pinfunction "C_C") (pintype "passive"))
      (node (ref "R2") (pin "P$2") (pinfunction "2_P$2") (pintype "passive"))
    )
    (net (code "32") (name "Net-(R4-2)") (class "Default")
      (node (ref "LED4") (pin "C") (pinfunction "C_C") (pintype "passive"))
      (node (ref "R4") (pin "P$2") (pinfunction "2_P$2") (pintype "passive"))
    )
    (net (code "33") (name "Net-(R21-2)") (class "Default")
      (node (ref "R21") (pin "P$2") (pinfunction "2_P$2") (pintype "passive"))
      (node (ref "TP2") (pin "TP") (pinfunction "TP_TP") (pintype "input"))
    )
    (net (code "34") (name "Net-(R24-2)") (class "Default")
      (node (ref "R24") (pin "P$2") (pinfunction "2_P$2") (pintype "passive"))
      (node (ref "TP3") (pin "TP") (pinfunction "TP_TP") (pintype "input"))
    )
    (net (code "35") (name "Net-(R37-1)") (class "Default")
      (node (ref "R37") (pin "P$1") (pinfunction "1_P$1") (pintype "passive"))
      (node (ref "U1") (pin "6") (pinfunction "OUT_6") (pintype "output"))
    )
    (net (code "36") (name "Net-(R52-2)") (class "Default")
      (node (ref "D1") (pin "C") (pinfunction "C_C") (pintype "passive"))
      (node (ref "R52") (pin "P$2") (pinfunction "2_P$2") (pintype "passive"))
    )
    (net (code "37") (name "Net-(R53-2)") (class "Default")
      (node (ref "D3") (pin "C") (pinfunction "C_C") (pintype "passive"))
      (node (ref "R53") (pin "P$2") (pinfunction "2_P$2") (pintype "passive"))
    )
    (net (code "38") (name "Net-(R54-2)") (class "Default")
      (node (ref "D4") (pin "C") (pinfunction "C_C") (pintype "passive"))
      (node (ref "R54") (pin "P$2") (pinfunction "2_P$2") (pintype "passive"))
    )
    (net (code "39") (name "PGND") (class "Default")
      (node (ref "C26") (pin "P$2") (pinfunction "2_P$2") (pintype "passive"))
      (node (ref "C27") (pin "P$2") (pinfunction "2_P$2") (pintype "passive"))
      (node (ref "C32") (pin "P$2") (pinfunction "2_P$2") (pintype "passive"))
      (node (ref "IC2") (pin "3") (pinfunction "COM_3") (pintype "passive"))
      (node (ref "IC5") (pin "3") (pinfunction "COM_3") (pintype "passive"))
      (node (ref "IC6") (pin "3") (pinfunction "COM_3") (pintype "passive"))
      (node (ref "Q2") (pin "1") (pinfunction "S3_1") (pintype "passive"))
      (node (ref "Q2") (pin "2") (pinfunction "S2_2") (pintype "passive"))
      (node (ref "Q2") (pin "3") (pinfunction "S1_3") (pintype "passive"))
      (node (ref "Q4") (pin "1") (pinfunction "S3_1") (pintype "passive"))
      (node (ref "Q4") (pin "2") (pinfunction "S2_2") (pintype "passive"))
      (node (ref "Q4") (pin "3") (pinfunction "S1_3") (pintype "passive"))
      (node (ref "Q6") (pin "1") (pinfunction "S3_1") (pintype "passive"))
      (node (ref "Q6") (pin "2") (pinfunction "S2_2") (pintype "passive"))
      (node (ref "Q6") (pin "3") (pinfunction "S1_3") (pintype "passive"))
      (node (ref "R27") (pin "P$2") (pinfunction "2_P$2") (pintype "passive"))
      (node (ref "R45") (pin "P$1") (pinfunction "1_P$1") (pintype "passive"))
    )
    (net (code "40") (name "PHASE_U") (class "Default")
      (node (ref "C23") (pin "P$2") (pinfunction "2_P$2") (pintype "passive"))
      (node (ref "IC2") (pin "6") (pinfunction "VS_6") (pintype "input"))
      (node (ref "PAD5") (pin "1") (pinfunction "P_1") (pintype "passive"))
      (node (ref "Q5") (pin "1") (pinfunction "S3_1") (pintype "passive"))
      (node (ref "Q5") (pin "2") (pinfunction "S2_2") (pintype "passive"))
      (node (ref "Q5") (pin "3") (pinfunction "S1_3") (pintype "passive"))
      (node (ref "Q6") (pin "5") (pinfunction "D1_5") (pintype "passive"))
      (node (ref "Q6") (pin "6") (pinfunction "D2_6") (pintype "passive"))
      (node (ref "Q6") (pin "7") (pinfunction "D3_7") (pintype "passive"))
      (node (ref "Q6") (pin "8") (pinfunction "D4_8") (pintype "passive"))
      (node (ref "R14") (pin "P$1") (pinfunction "1_P$1") (pintype "passive"))
    )
    (net (code "41") (name "PHASE_V") (class "Default")
      (node (ref "C24") (pin "P$2") (pinfunction "2_P$2") (pintype "passive"))
      (node (ref "IC5") (pin "6") (pinfunction "VS_6") (pintype "input"))
      (node (ref "PAD2") (pin "1") (pinfunction "P_1") (pintype "passive"))
      (node (ref "Q3") (pin "1") (pinfunction "S3_1") (pintype "passive"))
      (node (ref "Q3") (pin "2") (pinfunction "S2_2") (pintype "passive"))
      (node (ref "Q3") (pin "3") (pinfunction "S1_3") (pintype "passive"))
      (node (ref "Q4") (pin "5") (pinfunction "D1_5") (pintype "passive"))
      (node (ref "Q4") (pin "6") (pinfunction "D2_6") (pintype "passive"))
      (node (ref "Q4") (pin "7") (pinfunction "D3_7") (pintype "passive"))
      (node (ref "Q4") (pin "8") (pinfunction "D4_8") (pintype "passive"))
      (node (ref "R16") (pin "P$1") (pinfunction "1_P$1") (pintype "passive"))
    )
    (net (code "42") (name "PHASE_W") (class "Default")
      (node (ref "C25") (pin "P$2") (pinfunction "2_P$2") (pintype "passive"))
      (node (ref "IC6") (pin "6") (pinfunction "VS_6") (pintype "input"))
      (node (ref "PAD1") (pin "1") (pinfunction "P_1") (pintype "passive"))
      (node (ref "Q1") (pin "1") (pinfunction "S3_1") (pintype "passive"))
      (node (ref "Q1") (pin "2") (pinfunction "S2_2") (pintype "passive"))
      (node (ref "Q1") (pin "3") (pinfunction "S1_3") (pintype "passive"))
      (node (ref "Q2") (pin "5") (pinfunction "D1_5") (pintype "passive"))
      (node (ref "Q2") (pin "6") (pinfunction "D2_6") (pintype "passive"))
      (node (ref "Q2") (pin "7") (pinfunction "D3_7") (pintype "passive"))
      (node (ref "Q2") (pin "8") (pinfunction "D4_8") (pintype "passive"))
      (node (ref "R18") (pin "P$1") (pinfunction "1_P$1") (pintype "passive"))
    )
    (net (code "43") (name "RST") (class "Default")
      (node (ref "C6") (pin "P$2") (pinfunction "2_P$2") (pintype "passive"))
      (node (ref "IC7") (pin "7") (pinfunction "NRST_7") (pintype "bidirectional"))
    )
    (net (code "44") (name "RXD") (class "Default")
      (node (ref "IC7") (pin "43") (pinfunction "PB7-I2C1SDA/USART1RX/TIM17CH1N_43") (pintype "bidirectional"))
      (node (ref "R21") (pin "P$1") (pinfunction "1_P$1") (pintype "passive"))
    )
    (net (code "45") (name "TCK{slash}SWCLK") (class "Default")
      (node (ref "IC7") (pin "37") (pinfunction "PA14-SWCLK_37") (pintype "bidirectional"))
      (node (ref "TP12") (pin "TP") (pinfunction "TP_TP") (pintype "input"))
    )
    (net (code "46") (name "TDI") (class "Default")
      (node (ref "IC7") (pin "38") (pinfunction "PA15-SPI1NSS/I2S1WS/TIM2CH1ETR/EVENTOUT_38") (pintype "bidirectional"))
    )
    (net (code "47") (name "TDO{slash}TRACESWO") (class "Default")
      (node (ref "IC7") (pin "39") (pinfunction "PB3-SPI1SCK/I2S1CK/TIM2CH2/EVENTOUT_39") (pintype "bidirectional"))
      (node (ref "TP13") (pin "TP") (pinfunction "TP_TP") (pintype "input"))
    )
    (net (code "48") (name "TMS{slash}SWDIO") (class "Default")
      (node (ref "IC7") (pin "34") (pinfunction "PA13-IROUT/SWDIO_34") (pintype "bidirectional"))
      (node (ref "TP11") (pin "TP") (pinfunction "TP_TP") (pintype "input"))
    )
    (net (code "49") (name "TXD") (class "Default")
      (node (ref "IC7") (pin "42") (pinfunction "PB6-I2C1SCL/USART1TX/TIM16CH1N_42") (pintype "bidirectional"))
      (node (ref "R24") (pin "P$1") (pinfunction "1_P$1") (pintype "passive"))
    )
    (net (code "50") (name "USART_+5V") (class "Default")
      (node (ref "D2") (pin "A") (pinfunction "A_A") (pintype "passive"))
      (node (ref "TP4") (pin "TP") (pinfunction "TP_TP") (pintype "input"))
    )
    (net (code "51") (name "U_GATE_HIGH") (class "Default")
      (node (ref "IC2") (pin "7") (pinfunction "HO_7") (pintype "output"))
      (node (ref "R50") (pin "P$2") (pinfunction "2_P$2") (pintype "passive"))
    )
    (net (code "52") (name "U_GATE_LOW") (class "Default")
      (node (ref "IC2") (pin "4") (pinfunction "LO_4") (pintype "output"))
      (node (ref "R51") (pin "P$2") (pinfunction "2_P$2") (pintype "passive"))
    )
    (net (code "53") (name "U_PWM") (class "Default")
      (node (ref "IC7") (pin "29") (pinfunction "PA8-USART1CK/TIM1CH1/EVENTOUT/MCO_29") (pintype "bidirectional"))
      (node (ref "R5") (pin "P$2") (pinfunction "2_P$2") (pintype "passive"))
    )
    (net (code "54") (name "U_VOLTAGE") (class "Default")
      (node (ref "IC7") (pin "10") (pinfunction "PA0-TIM2CH1ETR-ADC0/RTC_TAMP2/WKUP1_10") (pintype "bidirectional"))
      (node (ref "R14") (pin "P$2") (pinfunction "2_P$2") (pintype "passive"))
      (node (ref "R15") (pin "P$1") (pinfunction "1_P$1") (pintype "passive"))
    )
    (net (code "55") (name "U_~{DIS}") (class "Default")
      (node (ref "IC7") (pin "26") (pinfunction "PB13-TIM1CH1N_26") (pintype "bidirectional"))
      (node (ref "R8") (pin "P$1") (pinfunction "1_P$1") (pintype "passive"))
    )
    (net (code "56") (name "V_BATT") (class "Default")
      (node (ref "IC7") (pin "13") (pinfunction "PA3-TIM2CH4-ADC3_13") (pintype "bidirectional"))
      (node (ref "R12") (pin "P$1") (pinfunction "1_P$1") (pintype "passive"))
      (node (ref "R13") (pin "P$2") (pinfunction "2_P$2") (pintype "passive"))
    )
    (net (code "57") (name "V_GATE_HIGH") (class "Default")
      (node (ref "IC5") (pin "7") (pinfunction "HO_7") (pintype "output"))
      (node (ref "R48") (pin "P$2") (pinfunction "2_P$2") (pintype "passive"))
    )
    (net (code "58") (name "V_GATE_LOW") (class "Default")
      (node (ref "IC5") (pin "4") (pinfunction "LO_4") (pintype "output"))
      (node (ref "R49") (pin "P$2") (pinfunction "2_P$2") (pintype "passive"))
    )
    (net (code "59") (name "V_IN") (class "Default")
      (node (ref "C1") (pin "+") (pinfunction "+_+") (pintype "passive"))
      (node (ref "C2") (pin "P$1") (pinfunction "1_P$1") (pintype "passive"))
      (node (ref "D2") (pin "C") (pinfunction "C_C") (pintype "passive"))
      (node (ref "IC1") (pin "1") (pinfunction "VIN_1") (pintype "bidirectional"))
      (node (ref "IC1") (pin "3") (pinfunction "ON/OFF_3") (pintype "bidirectional"))
      (node (ref "J3") (pin "P$1") (pinfunction "1_P$1") (pintype "passive"))
      (node (ref "TP8") (pin "TP") (pinfunction "TP_TP") (pintype "input"))
    )
    (net (code "60") (name "V_PWM") (class "Default")
      (node (ref "IC7") (pin "30") (pinfunction "PA9-USART1TX/TIM1CH2_30") (pintype "bidirectional"))
      (node (ref "R6") (pin "P$2") (pinfunction "2_P$2") (pintype "passive"))
    )
    (net (code "61") (name "V_VOLTAGE") (class "Default")
      (node (ref "IC7") (pin "11") (pinfunction "PA1-TIM2CH2/EVENTOUT-ADC1_11") (pintype "bidirectional"))
      (node (ref "R16") (pin "P$2") (pinfunction "2_P$2") (pintype "passive"))
      (node (ref "R17") (pin "P$1") (pinfunction "1_P$1") (pintype "passive"))
    )
    (net (code "62") (name "V_~{DIS}") (class "Default")
      (node (ref "IC7") (pin "27") (pinfunction "PB14-TIM1CH2N_27") (pintype "bidirectional"))
      (node (ref "R9") (pin "P$1") (pinfunction "1_P$1") (pintype "passive"))
    )
    (net (code "63") (name "W_GATE_HIGH") (class "Default")
      (node (ref "IC6") (pin "7") (pinfunction "HO_7") (pintype "output"))
      (node (ref "R46") (pin "P$2") (pinfunction "2_P$2") (pintype "passive"))
    )
    (net (code "64") (name "W_GATE_LOW") (class "Default")
      (node (ref "IC6") (pin "4") (pinfunction "LO_4") (pintype "output"))
      (node (ref "R47") (pin "P$2") (pinfunction "2_P$2") (pintype "passive"))
    )
    (net (code "65") (name "W_PWM") (class "Default")
      (node (ref "IC7") (pin "31") (pinfunction "PA10-USART1RX/TIM1CH3/TIM17BKIN_31") (pintype "bidirectional"))
      (node (ref "R7") (pin "P$2") (pinfunction "2_P$2") (pintype "passive"))
    )
    (net (code "66") (name "W_VOLTAGE") (class "Default")
      (node (ref "IC7") (pin "12") (pinfunction "PA2-TIM2CH3-ADC2_12") (pintype "bidirectional"))
      (node (ref "R18") (pin "P$2") (pinfunction "2_P$2") (pintype "passive"))
      (node (ref "R22") (pin "P$1") (pinfunction "1_P$1") (pintype "passive"))
    )
    (net (code "67") (name "W_~{DIS}") (class "Default")
      (node (ref "IC7") (pin "28") (pinfunction "PB15-TIM1CH3N-RTCREFIN_28") (pintype "bidirectional"))
      (node (ref "R10") (pin "P$1") (pinfunction "1_P$1") (pintype "passive"))
    )
    (net (code "68") (name "unconnected-(IC3-SHDN-Pad5)") (class "Default")
      (node (ref "IC3") (pin "5") (pinfunction "SHDN_5") (pintype "bidirectional"))
    )
    (net (code "69") (name "unconnected-(IC7-PA6-SPI1MISO{slash}I2S1MCK{slash}TIM3CH1{slash}TIM1BKIN{slash}TIM16CH1{slash}EVENTOUT-ADC6-Pad16)") (class "Default")
      (node (ref "IC7") (pin "16") (pinfunction "PA6-SPI1MISO/I2S1MCK/TIM3CH1/TIM1BKIN/TIM16CH1/EVENTOUT-ADC6_16") (pintype "bidirectional"))
    )
    (net (code "70") (name "unconnected-(IC7-PA7-SPI1MOSI{slash}I2S1SD{slash}TIM3CH2{slash}TIM14CH1{slash}TIM1CH1N{slash}TIM17CH1{slash}EVENTOUT-ADC7-Pad17)") (class "Default")
      (node (ref "IC7") (pin "17") (pinfunction "PA7-SPI1MOSI/I2S1SD/TIM3CH2/TIM14CH1/TIM1CH1N/TIM17CH1/EVENTOUT-ADC7_17") (pintype "bidirectional"))
    )
    (net (code "71") (name "unconnected-(IC7-PA11-USART1CTS{slash}TIM1CH4{slash}EVENTOUT-Pad32)") (class "Default")
      (node (ref "IC7") (pin "32") (pinfunction "PA11-USART1CTS/TIM1CH4/EVENTOUT_32") (pintype "bidirectional"))
    )
    (net (code "72") (name "unconnected-(IC7-PA12-USART1RTS{slash}TIM1ETR{slash}EVENTOUT-Pad33)") (class "Default")
      (node (ref "IC7") (pin "33") (pinfunction "PA12-USART1RTS/TIM1ETR/EVENTOUT_33") (pintype "bidirectional"))
    )
    (net (code "73") (name "unconnected-(IC7-PB0-TIM3CH3{slash}TIM1CH2N{slash}EVENTOUT-ADC8-Pad18)") (class "Default")
      (node (ref "IC7") (pin "18") (pinfunction "PB0-TIM3CH3/TIM1CH2N/EVENTOUT-ADC8_18") (pintype "bidirectional"))
    )
    (net (code "74") (name "unconnected-(IC7-PB1-TIM3CH4{slash}TIM14CH1{slash}TIM1CH3N-ADC9-Pad19)") (class "Default")
      (node (ref "IC7") (pin "19") (pinfunction "PB1-TIM3CH4/TIM14CH1/TIM1CH3N-ADC9_19") (pintype "bidirectional"))
    )
    (net (code "75") (name "unconnected-(IC7-PB2-Pad20)") (class "Default")
      (node (ref "IC7") (pin "20") (pinfunction "PB2_20") (pintype "bidirectional"))
    )
    (net (code "76") (name "unconnected-(IC7-PB10-TIM2CH3-Pad21)") (class "Default")
      (node (ref "IC7") (pin "21") (pinfunction "PB10-TIM2CH3_21") (pintype "bidirectional"))
    )
    (net (code "77") (name "unconnected-(IC7-PB11-TIM2CH4{slash}EVENTOUT-Pad22)") (class "Default")
      (node (ref "IC7") (pin "22") (pinfunction "PB11-TIM2CH4/EVENTOUT_22") (pintype "bidirectional"))
    )
    (net (code "78") (name "unconnected-(IC7-PB12-TIM1BKIN{slash}EVENTOUT-Pad25)") (class "Default")
      (node (ref "IC7") (pin "25") (pinfunction "PB12-TIM1BKIN/EVENTOUT_25") (pintype "bidirectional"))
    )
    (net (code "79") (name "unconnected-(IC7-PC13-RTC_TMAMP1{slash}RTC_TS{slash}RTC_OUT{slash}WKUP2-Pad2)") (class "Default")
      (node (ref "IC7") (pin "2") (pinfunction "PC13-RTC_TMAMP1/RTC_TS/RTC_OUT/WKUP2_2") (pintype "bidirectional"))
    )
    (net (code "80") (name "unconnected-(IC7-PC14-OSC32_IN-Pad3)") (class "Default")
      (node (ref "IC7") (pin "3") (pinfunction "PC14-OSC32_IN_3") (pintype "bidirectional"))
    )
    (net (code "81") (name "unconnected-(IC7-PC15-OSC32_OUT-Pad4)") (class "Default")
      (node (ref "IC7") (pin "4") (pinfunction "PC15-OSC32_OUT_4") (pintype "bidirectional"))
    )
    (net (code "82") (name "unconnected-(IC7-PF0-OSC_IN-Pad5)") (class "Default")
      (node (ref "IC7") (pin "5") (pinfunction "PF0-OSC_IN_5") (pintype "input"))
    )
    (net (code "83") (name "unconnected-(IC7-PF1-OSC_OUT-Pad6)") (class "Default")
      (node (ref "IC7") (pin "6") (pinfunction "PF1-OSC_OUT_6") (pintype "output"))
    )
  )
)
